# treehopper-mini.net
KiCad netlist of a schematic drawn in Altium Designer
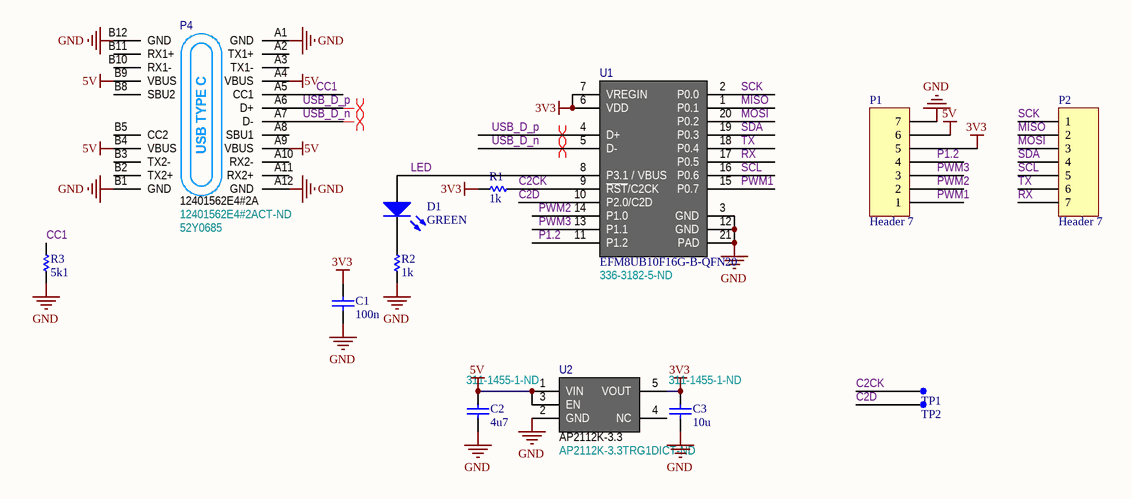
[diagram p0: treehopper-mini.SchDoc]

(export (version "E")
  (design (tool "Eeschema 10.0.6"))
  (components
    (comp (ref "C1")
      (value "100n")
      (footprint "CAPC1005N")
      (description "Capacitor (Semiconductor SIM Model)")
      (fields (field (name "PUBLISHER") "Altium Limited"))
      (libsource (lib "Miscellaneous Devices") (part "Cap Semi"))
    )
    (comp (ref "C2")
      (value "4u7")
      (footprint "CAPC1608N")
      (description "CAP SEMI 4U7 10V 0603")
      (fields
        (field (name "SUPPLIER PART NUMBER 1") "311-1455-1-ND")
        (field (name "PUBLISHER") "Altium Limited")
      )
      (libsource (lib "Miscellaneous Devices") (part "Cap Semi"))
    )
    (comp (ref "C3")
      (value "10u")
      (footprint "CAPC1608N")
      (description "CAP SEMI 4U7 10V 0603")
      (fields
        (field (name "SUPPLIER PART NUMBER 1") "311-1455-1-ND")
        (field (name "PUBLISHER") "Altium Limited")
      )
      (libsource (lib "Miscellaneous Devices") (part "Cap Semi"))
    )
    (comp (ref "D1")
      (value "GREEN")
      (footprint "LTST-C190GKT_NO_SILK")
      (description "Typical greenGaAs LED")
      (fields (field (name "PUBLISHER") "Altium Limited"))
      (libsource (lib "Miscellaneous Devices") (part "LED_GREEN"))
    )
    (comp (ref "P1")
      (value "Header 7")
      (footprint "HDR1X7_CASTELATED")
      (description "Header, 7-Pin")
      (fields (field (name "PUBLISHER") "Altium Limited"))
      (libsource (lib "Miscellaneous Connectors") (part "Header 7"))
    )
    (comp (ref "P2")
      (value "Header 7")
      (footprint "HDR1X7_CASTELATED")
      (description "Header, 7-Pin")
      (fields (field (name "PUBLISHER") "Altium Limited"))
      (libsource (lib "") (part "Header 7_1"))
    )
    (comp (ref "P4")
      (value "12401562E4#2A")
      (footprint "12401562E4#2A")
      (description "USB TYPE C PLUG")
      (fields
        (field (name "MANUFACTURER") "Amphenol Commercial Products")
        (field (name "SUPPLIER PART NUMBER 1") "12401562E4#2ACT-ND")
        (field (name "SUPPLIER PART NUMBER 2") "52Y0685")
      )
      (libsource (lib "Amphenol USB Connector") (part "12401562E4#2A"))
    )
    (comp (ref "R1")
      (value "1k")
      (footprint "RESC1005N")
      (description "Semiconductor Resistor")
      (fields (field (name "PUBLISHER") "Altium Limited"))
      (libsource (lib "Miscellaneous Devices") (part "Res Semi"))
    )
    (comp (ref "R2")
      (value "1k")
      (footprint "RESC1005N")
      (description "Semiconductor Resistor")
      (fields (field (name "PUBLISHER") "Altium Limited"))
      (libsource (lib "Miscellaneous Devices") (part "Res Semi"))
    )
    (comp (ref "R3")
      (value "5k1")
      (footprint "RESC1005N")
      (description "Semiconductor Resistor")
      (fields (field (name "PUBLISHER") "Altium Limited"))
      (libsource (lib "Miscellaneous Devices") (part "Res Semi"))
    )
    (comp (ref "TP1")
      (value "TESTPOINT")
      (footprint "TESTPOINT100")
      (description "Testpoint")
      (fields (field (name "PUBLISHER") "Altium Limited"))
      (libsource (lib "Miscellaneous Connectors") (part "TESTPOINT"))
    )
    (comp (ref "TP2")
      (value "TESTPOINT")
      (footprint "TESTPOINT100")
      (description "Testpoint")
      (fields (field (name "PUBLISHER") "Altium Limited"))
      (libsource (lib "Miscellaneous Connectors") (part "TESTPOINT"))
    )
    (comp (ref "U1")
      (value "EFM8UB10F16G-B-QFN20")
      (footprint "QFN50P300X300X90-20N-NO-SILK")
      (description "IC MCU 16KB 20QFN")
      (fields
        (field (name "MANUFACTURER") "Silicon Labs")
        (field (name "SUPPLIER PART NUMBER 1") "336-3182-5-ND")
      )
      (libsource (lib "SiLabs EFM8 MCU") (part "EFM8UB10F16G-B-QFN20"))
    )
    (comp (ref "U2")
      (value "AP2112K-3.3")
      (footprint "SOT23-5AN-no-silk")
      (description "AP2112 IC REG LDO 3.3V 0.6A SOT25")
      (fields
        (field (name "MANUFACTURER") "Diodes Incorporated")
        (field (name "MANUFACTURER PART NUMBER") "AP2112K-3.3TRG1")
        (field (name "SUPPLIER PART NUMBER 1") "AP2112K-3.3TRG1DICT-ND")
      )
      (libsource (lib "Diodes Inc LDO Regulator") (part "AP2112K-3.3"))
    )
  )
  (nets
    (net (code "1") (name "/C2CK") (class "Default")
      (node (ref "R1") (pin "1") (pinfunction "1_1") (pintype "passive"))
      (node (ref "TP1") (pin "1") (pinfunction "TP_1") (pintype "passive"))
      (node (ref "U1") (pin "9") (pinfunction "~{RST}/C2CK_9") (pintype "passive"))
    )
    (net (code "2") (name "/C2D") (class "Default")
      (node (ref "TP2") (pin "1") (pinfunction "TP_1") (pintype "passive"))
      (node (ref "U1") (pin "10") (pinfunction "P2.0/C2D_10") (pintype "passive"))
    )
    (net (code "3") (name "/CC1") (class "Default")
      (node (ref "P4") (pin "A5") (pinfunction "CC1_A5") (pintype "power_in"))
      (node (ref "R3") (pin "2") (pinfunction "2_2") (pintype "passive"))
    )
    (net (code "4") (name "/LED") (class "Default")
      (node (ref "D1") (pin "1") (pinfunction "A_1") (pintype "passive"))
      (node (ref "U1") (pin "8") (pinfunction "P3.1_/_VBUS_8") (pintype "passive"))
    )
    (net (code "5") (name "/MISO") (class "Default")
      (node (ref "P2") (pin "2") (pinfunction "2_2") (pintype "passive"))
      (node (ref "U1") (pin "1") (pinfunction "P0.1_1") (pintype "passive"))
    )
    (net (code "6") (name "/MOSI") (class "Default")
      (node (ref "P2") (pin "3") (pinfunction "3_3") (pintype "passive"))
      (node (ref "U1") (pin "20") (pinfunction "P0.2_20") (pintype "passive"))
    )
    (net (code "7") (name "/P1.2") (class "Default")
      (node (ref "P1") (pin "4") (pinfunction "4_4") (pintype "passive"))
      (node (ref "U1") (pin "11") (pinfunction "P1.2_11") (pintype "passive"))
    )
    (net (code "8") (name "/PWM1") (class "Default")
      (node (ref "P1") (pin "1") (pinfunction "1_1") (pintype "passive"))
      (node (ref "U1") (pin "15") (pinfunction "P0.7_15") (pintype "passive"))
    )
    (net (code "9") (name "/PWM2") (class "Default")
      (node (ref "P1") (pin "2") (pinfunction "2_2") (pintype "passive"))
      (node (ref "U1") (pin "14") (pinfunction "P1.0_14") (pintype "passive"))
    )
    (net (code "10") (name "/PWM3") (class "Default")
      (node (ref "P1") (pin "3") (pinfunction "3_3") (pintype "passive"))
      (node (ref "U1") (pin "13") (pinfunction "P1.1_13") (pintype "passive"))
    )
    (net (code "11") (name "/RX") (class "Default")
      (node (ref "P2") (pin "7") (pinfunction "7_7") (pintype "passive"))
      (node (ref "U1") (pin "17") (pinfunction "P0.5_17") (pintype "passive"))
    )
    (net (code "12") (name "/SCK") (class "Default")
      (node (ref "P2") (pin "1") (pinfunction "1_1") (pintype "passive"))
      (node (ref "U1") (pin "2") (pinfunction "P0.0_2") (pintype "passive"))
    )
    (net (code "13") (name "/SCL") (class "Default")
      (node (ref "P2") (pin "5") (pinfunction "5_5") (pintype "passive"))
      (node (ref "U1") (pin "16") (pinfunction "P0.6_16") (pintype "passive"))
    )
    (net (code "14") (name "/SDA") (class "Default")
      (node (ref "P2") (pin "4") (pinfunction "4_4") (pintype "passive"))
      (node (ref "U1") (pin "19") (pinfunction "P0.3_19") (pintype "passive"))
    )
    (net (code "15") (name "/TX") (class "Default")
      (node (ref "P2") (pin "6") (pinfunction "6_6") (pintype "passive"))
      (node (ref "U1") (pin "18") (pinfunction "P0.4_18") (pintype "passive"))
    )
    (net (code "16") (name "/USB_D_n") (class "Default")
      (node (ref "P4") (pin "A7") (pinfunction "D-_A7") (pintype "power_in"))
      (node (ref "U1") (pin "5") (pinfunction "D-_5") (pintype "passive"))
    )
    (net (code "17") (name "/USB_D_p") (class "Default")
      (node (ref "P4") (pin "A6") (pinfunction "D+_A6") (pintype "power_in"))
      (node (ref "U1") (pin "4") (pinfunction "D+_4") (pintype "passive"))
    )
    (net (code "18") (name "3V3") (class "Default")
      (node (ref "C1") (pin "2") (pinfunction "2_2") (pintype "passive"))
      (node (ref "C3") (pin "2") (pinfunction "2_2") (pintype "passive"))
      (node (ref "P1") (pin "5") (pinfunction "5_5") (pintype "passive"))
      (node (ref "R1") (pin "2") (pinfunction "2_2") (pintype "passive"))
      (node (ref "U1") (pin "6") (pinfunction "VDD_6") (pintype "passive"))
      (node (ref "U1") (pin "7") (pinfunction "VREGIN_7") (pintype "passive"))
      (node (ref "U2") (pin "5") (pinfunction "VOUT_5") (pintype "passive"))
    )
    (net (code "19") (name "5V") (class "Default")
      (node (ref "C2") (pin "2") (pinfunction "2_2") (pintype "passive"))
      (node (ref "P1") (pin "6") (pinfunction "6_6") (pintype "passive"))
      (node (ref "P4") (pin "A4") (pinfunction "VBUS_A4") (pintype "power_in"))
      (node (ref "P4") (pin "A9") (pinfunction "VBUS_A9") (pintype "power_in"))
      (node (ref "P4") (pin "B4") (pinfunction "VBUS_B4") (pintype "power_in"))
      (node (ref "P4") (pin "B9") (pinfunction "VBUS_B9") (pintype "power_in"))
      (node (ref "U2") (pin "1") (pinfunction "VIN_1") (pintype "passive"))
      (node (ref "U2") (pin "3") (pinfunction "EN_3") (pintype "passive"))
    )
    (net (code "20") (name "GND") (class "Default")
      (node (ref "C1") (pin "1") (pinfunction "1_1") (pintype "passive"))
      (node (ref "C2") (pin "1") (pinfunction "1_1") (pintype "passive"))
      (node (ref "C3") (pin "1") (pinfunction "1_1") (pintype "passive"))
      (node (ref "P1") (pin "7") (pinfunction "7_7") (pintype "passive"))
      (node (ref "P4") (pin "A1") (pinfunction "GND_A1") (pintype "power_in"))
      (node (ref "P4") (pin "A12") (pinfunction "GND_A12") (pintype "power_in"))
      (node (ref "P4") (pin "B1") (pinfunction "GND_B1") (pintype "power_in"))
      (node (ref "P4") (pin "B12") (pinfunction "GND_B12") (pintype "power_in"))
      (node (ref "R2") (pin "1") (pinfunction "1_1") (pintype "passive"))
      (node (ref "R3") (pin "1") (pinfunction "1_1") (pintype "passive"))
      (node (ref "U1") (pin "12") (pinfunction "GND_12") (pintype "passive"))
      (node (ref "U1") (pin "21") (pinfunction "PAD_21") (pintype "passive"))
      (node (ref "U1") (pin "3") (pinfunction "GND_3") (pintype "passive"))
      (node (ref "U2") (pin "2") (pinfunction "GND_2") (pintype "passive"))
    )
    (net (code "21") (name "Net-(D1-K)") (class "Default")
      (node (ref "D1") (pin "2") (pinfunction "K_2") (pintype "passive"))
      (node (ref "R2") (pin "2") (pinfunction "2_2") (pintype "passive"))
    )
    (net (code "22") (name "unconnected-(P4-CC2-PadB5)") (class "Default")
      (node (ref "P4") (pin "B5") (pinfunction "CC2_B5") (pintype "power_in"))
    )
    (net (code "23") (name "unconnected-(P4-RX1+-PadB11)") (class "Default")
      (node (ref "P4") (pin "B11") (pinfunction "RX1+_B11") (pintype "power_in"))
    )
    (net (code "24") (name "unconnected-(P4-RX1--PadB10)") (class "Default")
      (node (ref "P4") (pin "B10") (pinfunction "RX1-_B10") (pintype "power_in"))
    )
    (net (code "25") (name "unconnected-(P4-RX2+-PadA11)") (class "Default")
      (node (ref "P4") (pin "A11") (pinfunction "RX2+_A11") (pintype "power_in"))
    )
    (net (code "26") (name "unconnected-(P4-RX2--PadA10)") (class "Default")
      (node (ref "P4") (pin "A10") (pinfunction "RX2-_A10") (pintype "power_in"))
    )
    (net (code "27") (name "unconnected-(P4-SBU1-PadA8)") (class "Default")
      (node (ref "P4") (pin "A8") (pinfunction "SBU1_A8") (pintype "power_in"))
    )
    (net (code "28") (name "unconnected-(P4-SBU2-PadB8)") (class "Default")
      (node (ref "P4") (pin "B8") (pinfunction "SBU2_B8") (pintype "power_in"))
    )
    (net (code "29") (name "unconnected-(P4-TX1+-PadA2)") (class "Default")
      (node (ref "P4") (pin "A2") (pinfunction "TX1+_A2") (pintype "power_in"))
    )
    (net (code "30") (name "unconnected-(P4-TX1--PadA3)") (class "Default")
      (node (ref "P4") (pin "A3") (pinfunction "TX1-_A3") (pintype "power_in"))
    )
    (net (code "31") (name "unconnected-(P4-TX2+-PadB2)") (class "Default")
      (node (ref "P4") (pin "B2") (pinfunction "TX2+_B2") (pintype "power_in"))
    )
    (net (code "32") (name "unconnected-(P4-TX2--PadB3)") (class "Default")
      (node (ref "P4") (pin "B3") (pinfunction "TX2-_B3") (pintype "power_in"))
    )
    (net (code "33") (name "unconnected-(U2-NC-Pad4)") (class "Default")
      (node (ref "U2") (pin "4") (pinfunction "NC_4") (pintype "passive"))
    )
  )
)
